# VAR-PBB_v01.net
KiCad netlist of a schematic drawn in EAGLE
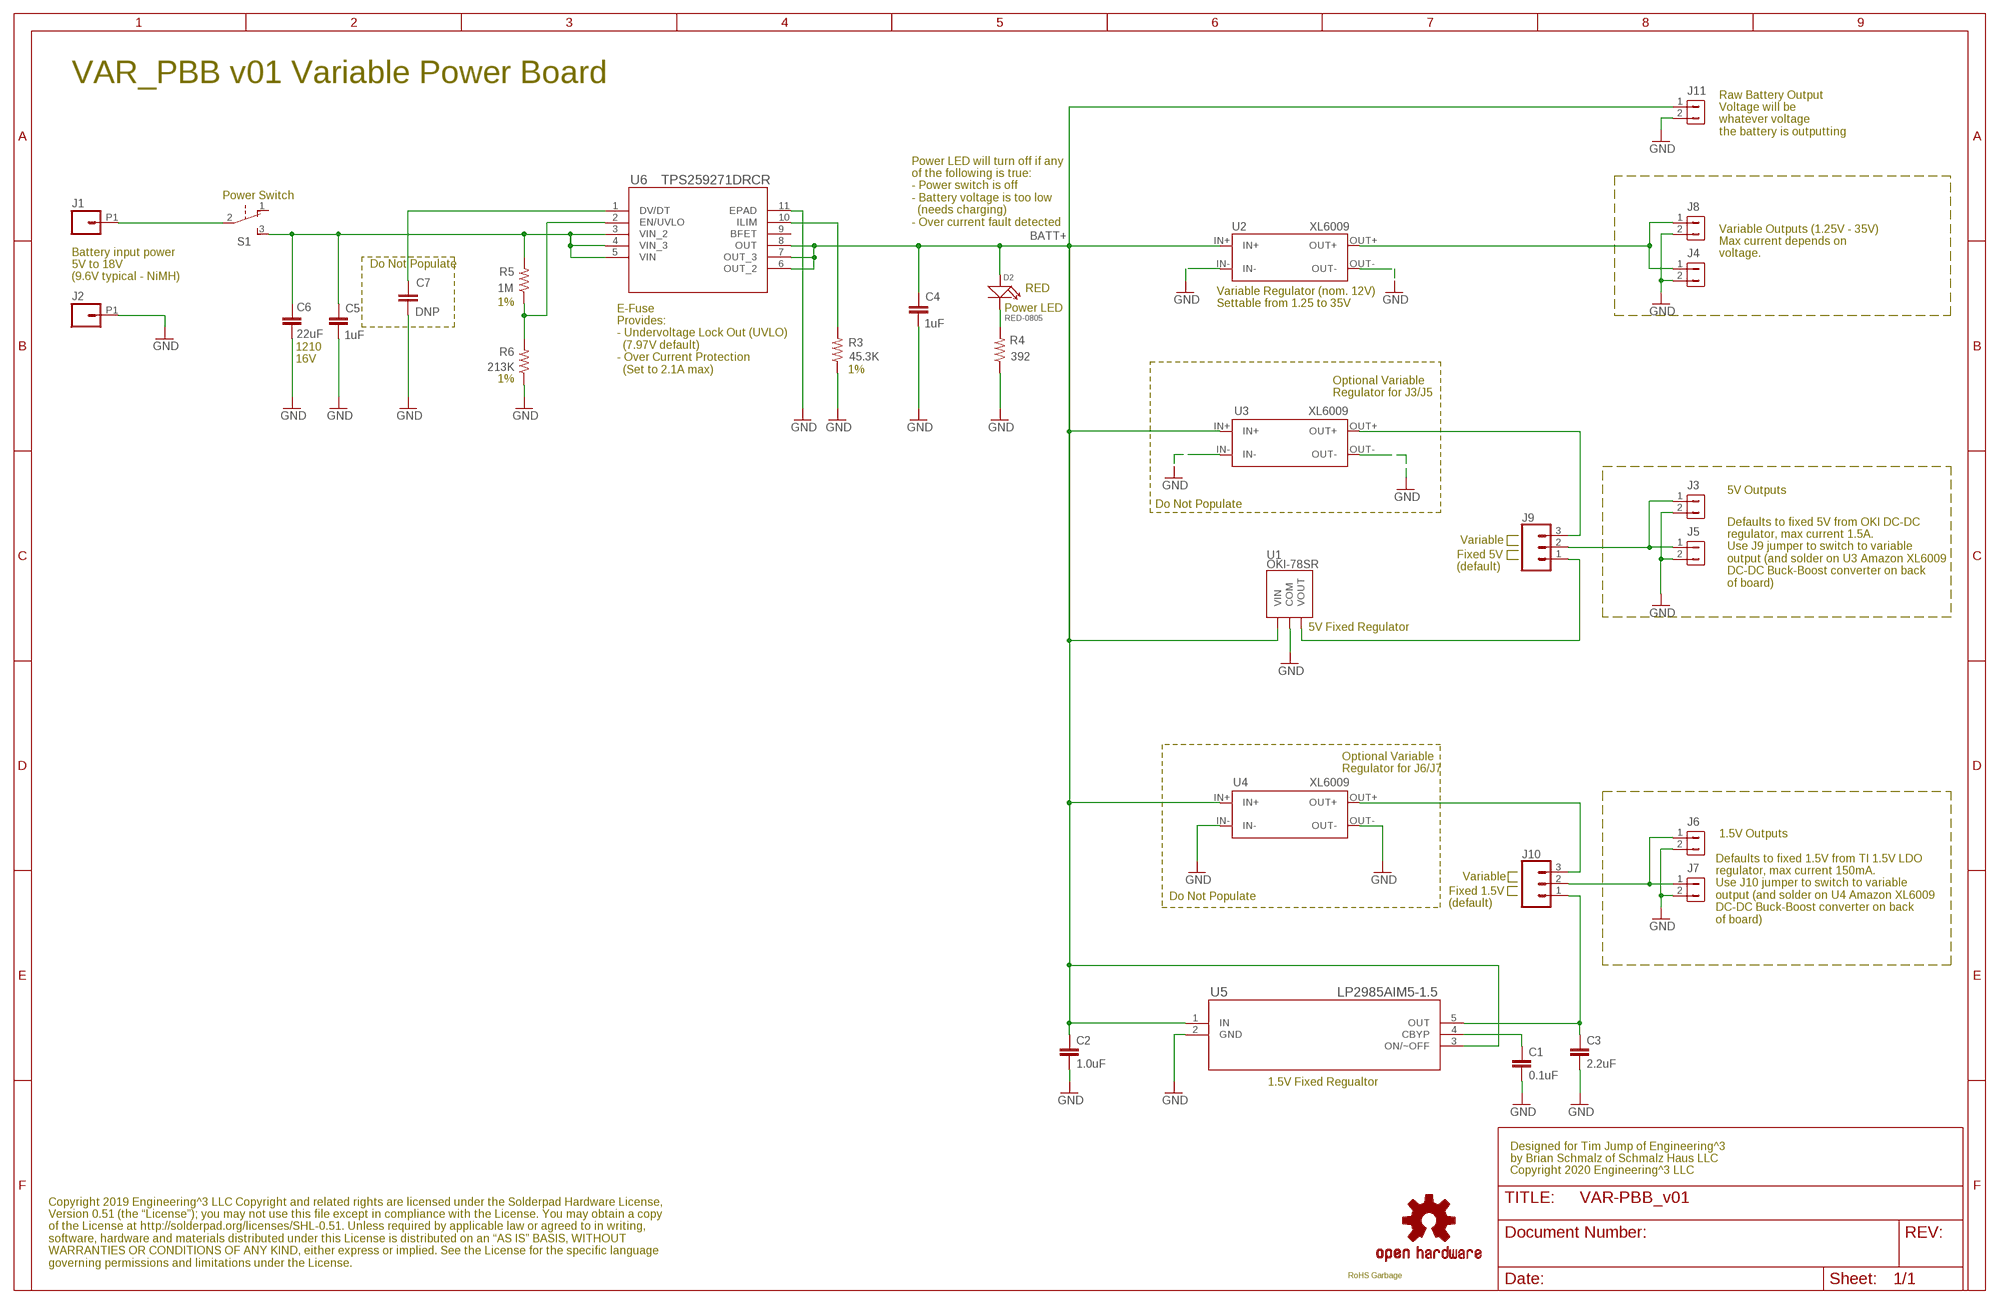
[diagram p0: schematic, sheet 1]

(export (version "E")
  (design (tool "Eeschema 10.0.6"))
  (components
    (comp (ref "C1")
      (value "0.1uF")
      (footprint "eagle-import:0603")
      (libsource (lib "eagle-import") (part "0.1UF-0603-25V-5%"))
    )
    (comp (ref "C2")
      (value "1.0uF")
      (footprint "eagle-import:0603")
      (libsource (lib "eagle-import") (part "1.0UF-0603-16V-10%"))
    )
    (comp (ref "C3")
      (value "2.2uF")
      (footprint "eagle-import:0603")
      (libsource (lib "eagle-import") (part "2.2UF-0603-10V-20%"))
    )
    (comp (ref "C4")
      (value "1uF")
      (footprint "eagle-import:0603")
      (libsource (lib "eagle-import") (part "0.1UF-0603-25V-5%"))
    )
    (comp (ref "C5")
      (value "1uF")
      (footprint "eagle-import:0603")
      (libsource (lib "eagle-import") (part "0.1UF-0603-25V-5%"))
    )
    (comp (ref "C6")
      (value "22uF")
      (footprint "eagle-import:1210")
      (libsource (lib "eagle-import") (part "22UF-1210-16V-20%"))
    )
    (comp (ref "C7")
      (value "DNP")
      (footprint "eagle-import:0603")
      (libsource (lib "eagle-import") (part "0.1UF-0603-25V-5%"))
    )
    (comp (ref "D2")
      (value "RED-0805")
      (footprint "eagle-import:LED-0805")
      (fields (field (name "MPN") "17-215SURC/S530-A2/TR8"))
      (libsource (lib "eagle-import") (part "SMD-LED-CLEAR-RED(0805)"))
    )
    (comp (ref "J1")
      (value "ANDERSON_POWER_POLE")
      (footprint "eagle-import:ANDERSON_POWER_POLE")
      (libsource (lib "eagle-import") (part "ANDERSON_POWER_POLE"))
    )
    (comp (ref "J2")
      (value "ANDERSON_POWER_POLE")
      (footprint "eagle-import:ANDERSON_POWER_POLE")
      (libsource (lib "eagle-import") (part "ANDERSON_POWER_POLE"))
    )
    (comp (ref "J3")
      (value "CON1X2_SHROUDED")
      (footprint "eagle-import:HEADER_1X2_SHROUDED")
      (libsource (lib "eagle-import") (part "CON1X2_SHROUDED"))
    )
    (comp (ref "J4")
      (value "CON1X2_SHROUDED")
      (footprint "eagle-import:HEADER_1X2_SHROUDED")
      (libsource (lib "eagle-import") (part "CON1X2_SHROUDED"))
    )
    (comp (ref "J5")
      (value "CON1X2_SHROUDED")
      (footprint "eagle-import:HEADER_1X2_SHROUDED")
      (libsource (lib "eagle-import") (part "CON1X2_SHROUDED"))
    )
    (comp (ref "J6")
      (value "CON1X2_SHROUDED")
      (footprint "eagle-import:HEADER_1X2_SHROUDED")
      (libsource (lib "eagle-import") (part "CON1X2_SHROUDED"))
    )
    (comp (ref "J7")
      (value "CON1X2_SHROUDED")
      (footprint "eagle-import:HEADER_1X2_SHROUDED")
      (libsource (lib "eagle-import") (part "CON1X2_SHROUDED"))
    )
    (comp (ref "J8")
      (value "CON1X2_SHROUDED")
      (footprint "eagle-import:HEADER_1X2_SHROUDED")
      (libsource (lib "eagle-import") (part "CON1X2_SHROUDED"))
    )
    (comp (ref "J9")
      (value "CONN_03")
      (footprint "eagle-import:1X03")
      (libsource (lib "eagle-import") (part "CONN_03"))
    )
    (comp (ref "J10")
      (value "CONN_03")
      (footprint "eagle-import:1X03")
      (libsource (lib "eagle-import") (part "CONN_03"))
    )
    (comp (ref "J11")
      (value "CON1X2_SHROUDED")
      (footprint "eagle-import:HEADER_1X2_SHROUDED")
      (libsource (lib "eagle-import") (part "CON1X2_SHROUDED"))
    )
    (comp (ref "LOGO2")
      (value "OSHW-LOGOM")
      (footprint "eagle-import:OSHW-LOGO-M")
      (libsource (lib "eagle-import") (part "OSHW-LOGOM"))
    )
    (comp (ref "R3")
      (value "45.3K")
      (footprint "eagle-import:0603")
      (libsource (lib "eagle-import") (part "RESISTOR0603"))
    )
    (comp (ref "R4")
      (value "392")
      (footprint "eagle-import:0603")
      (libsource (lib "eagle-import") (part "RESISTOR0603"))
    )
    (comp (ref "R5")
      (value "1M")
      (footprint "eagle-import:0603")
      (libsource (lib "eagle-import") (part "RESISTOR0603"))
    )
    (comp (ref "R6")
      (value "213K")
      (footprint "eagle-import:0603")
      (libsource (lib "eagle-import") (part "RESISTOR0603"))
    )
    (comp (ref "S1")
      (value "SWITCH_SLIDE_ON_ON")
      (footprint "eagle-import:SWITCH_SLIDE_RA")
      (libsource (lib "eagle-import") (part "SWITCH_SLIDE_ON_ON"))
    )
    (comp (ref "U$6")
      (value "ROHS_GARBAGE")
      (footprint "eagle-import:ROHS_GARBAGE_5MM")
      (libsource (lib "eagle-import") (part "ROHS_GARBAGE"))
    )
    (comp (ref "U1")
      (value "OKI-78SR")
      (footprint "eagle-import:OKI-78SR_REGULATOR_HORIZONTAL")
      (libsource (lib "eagle-import") (part "OKI-78SR"))
    )
    (comp (ref "U2")
      (value "XL6009")
      (footprint "eagle-import:XL6009_MODULE")
      (libsource (lib "eagle-import") (part "XL6009"))
    )
    (comp (ref "U3")
      (value "XL6009")
      (footprint "eagle-import:XL6009_MODULE")
      (libsource (lib "eagle-import") (part "XL6009"))
    )
    (comp (ref "U4")
      (value "XL6009")
      (footprint "eagle-import:XL6009_MODULE")
      (libsource (lib "eagle-import") (part "XL6009"))
    )
    (comp (ref "U5")
      (value "LP2985AIM5-1.5")
      (footprint "eagle-import:MF05A")
      (fields (field (name "COPYRIGHT") "Copyright (C) 2018 Accelerated Designs. All rights reserved"))
      (libsource (lib "eagle-import") (part "LP2985AIM5-1.5"))
    )
    (comp (ref "U6")
      (value "TPS259271DRCR")
      (footprint "eagle-import:DRC10_1P65X2P40")
      (fields (field (name "COPYRIGHT") "Copyright (C) 2018 Accelerated Designs. All rights reserved"))
      (libsource (lib "eagle-import") (part "TPS259271DRCR"))
    )
  )
  (nets
    (net (code "1") (name "/BATT+") (class "Default")
      (node (ref "C2") (pin "1") (pinfunction "1_1") (pintype "passive"))
      (node (ref "C4") (pin "2") (pinfunction "2_2") (pintype "passive"))
      (node (ref "D2") (pin "+") (pinfunction "+_+") (pintype "passive"))
      (node (ref "J11") (pin "1") (pinfunction "1_1") (pintype "passive"))
      (node (ref "U1") (pin "P$1") (pinfunction "VIN_P$1") (pintype "bidirectional"))
      (node (ref "U2") (pin "IN+") (pinfunction "IN+_IN+") (pintype "bidirectional"))
      (node (ref "U3") (pin "IN+") (pinfunction "IN+_IN+") (pintype "bidirectional"))
      (node (ref "U4") (pin "IN+") (pinfunction "IN+_IN+") (pintype "bidirectional"))
      (node (ref "U5") (pin "1") (pinfunction "IN_1") (pintype "power_in"))
      (node (ref "U5") (pin "3") (pinfunction "ON/~{OFF}_3") (pintype "input"))
      (node (ref "U6") (pin "6") (pinfunction "OUT_2_6") (pintype "output"))
      (node (ref "U6") (pin "7") (pinfunction "OUT_3_7") (pintype "output"))
      (node (ref "U6") (pin "8") (pinfunction "OUT_8") (pintype "output"))
    )
    (net (code "2") (name "GND") (class "Default")
      (node (ref "C1") (pin "2") (pinfunction "2_2") (pintype "passive"))
      (node (ref "C2") (pin "2") (pinfunction "2_2") (pintype "passive"))
      (node (ref "C3") (pin "2") (pinfunction "2_2") (pintype "passive"))
      (node (ref "C4") (pin "1") (pinfunction "1_1") (pintype "passive"))
      (node (ref "C5") (pin "1") (pinfunction "1_1") (pintype "passive"))
      (node (ref "C6") (pin "2") (pinfunction "2_2") (pintype "passive"))
      (node (ref "C7") (pin "1") (pinfunction "1_1") (pintype "passive"))
      (node (ref "J11") (pin "2") (pinfunction "2_2") (pintype "passive"))
      (node (ref "J2") (pin "P1") (pinfunction "5_P1") (pintype "passive"))
      (node (ref "J3") (pin "2") (pinfunction "2_2") (pintype "passive"))
      (node (ref "J4") (pin "2") (pinfunction "2_2") (pintype "passive"))
      (node (ref "J5") (pin "2") (pinfunction "2_2") (pintype "passive"))
      (node (ref "J6") (pin "2") (pinfunction "2_2") (pintype "passive"))
      (node (ref "J7") (pin "2") (pinfunction "2_2") (pintype "passive"))
      (node (ref "J8") (pin "2") (pinfunction "2_2") (pintype "passive"))
      (node (ref "R3") (pin "1") (pinfunction "1_1") (pintype "passive"))
      (node (ref "R4") (pin "1") (pinfunction "1_1") (pintype "passive"))
      (node (ref "R6") (pin "1") (pinfunction "1_1") (pintype "passive"))
      (node (ref "U1") (pin "P$2") (pinfunction "COM_P$2") (pintype "bidirectional"))
      (node (ref "U2") (pin "IN-") (pinfunction "IN-_IN-") (pintype "bidirectional"))
      (node (ref "U2") (pin "OUT-") (pinfunction "OUT-_OUT-") (pintype "bidirectional"))
      (node (ref "U3") (pin "IN-") (pinfunction "IN-_IN-") (pintype "bidirectional"))
      (node (ref "U3") (pin "OUT-") (pinfunction "OUT-_OUT-") (pintype "bidirectional"))
      (node (ref "U4") (pin "IN-") (pinfunction "IN-_IN-") (pintype "bidirectional"))
      (node (ref "U4") (pin "OUT-") (pinfunction "OUT-_OUT-") (pintype "bidirectional"))
      (node (ref "U5") (pin "2") (pinfunction "GND_2") (pintype "power_in"))
      (node (ref "U6") (pin "11") (pinfunction "EPAD_11") (pintype "passive"))
    )
    (net (code "3") (name "Net-(D2-Pad-)") (class "Default")
      (node (ref "D2") (pin "-") (pinfunction "-_-") (pintype "passive"))
      (node (ref "R4") (pin "2") (pinfunction "2_2") (pintype "passive"))
    )
    (net (code "4") (name "Net-(J1-5)") (class "Default")
      (node (ref "J1") (pin "P1") (pinfunction "5_P1") (pintype "passive"))
      (node (ref "S1") (pin "2") (pinfunction "P_2") (pintype "passive"))
    )
    (net (code "5") (name "Net-(J3-Pad1)") (class "Default")
      (node (ref "J3") (pin "1") (pinfunction "1_1") (pintype "passive"))
      (node (ref "J5") (pin "1") (pinfunction "1_1") (pintype "passive"))
      (node (ref "J9") (pin "2") (pinfunction "2_2") (pintype "passive"))
    )
    (net (code "6") (name "Net-(J4-Pad1)") (class "Default")
      (node (ref "J4") (pin "1") (pinfunction "1_1") (pintype "passive"))
      (node (ref "J8") (pin "1") (pinfunction "1_1") (pintype "passive"))
      (node (ref "U2") (pin "OUT+") (pinfunction "OUT+_OUT+") (pintype "bidirectional"))
    )
    (net (code "7") (name "Net-(J9-Pad3)") (class "Default")
      (node (ref "J9") (pin "3") (pinfunction "3_3") (pintype "passive"))
      (node (ref "U3") (pin "OUT+") (pinfunction "OUT+_OUT+") (pintype "bidirectional"))
    )
    (net (code "8") (name "Net-(J10-Pad2)") (class "Default")
      (node (ref "J10") (pin "2") (pinfunction "2_2") (pintype "passive"))
      (node (ref "J6") (pin "1") (pinfunction "1_1") (pintype "passive"))
      (node (ref "J7") (pin "1") (pinfunction "1_1") (pintype "passive"))
    )
    (net (code "9") (name "Net-(J10-Pad3)") (class "Default")
      (node (ref "J10") (pin "3") (pinfunction "3_3") (pintype "passive"))
      (node (ref "U4") (pin "OUT+") (pinfunction "OUT+_OUT+") (pintype "bidirectional"))
    )
    (net (code "10") (name "Net-(S1-S)") (class "Default")
      (node (ref "C5") (pin "2") (pinfunction "2_2") (pintype "passive"))
      (node (ref "C6") (pin "1") (pinfunction "1_1") (pintype "passive"))
      (node (ref "R5") (pin "2") (pinfunction "2_2") (pintype "passive"))
      (node (ref "S1") (pin "3") (pinfunction "S_3") (pintype "passive"))
      (node (ref "U6") (pin "3") (pinfunction "VIN_2_3") (pintype "passive"))
      (node (ref "U6") (pin "4") (pinfunction "VIN_3_4") (pintype "passive"))
      (node (ref "U6") (pin "5") (pinfunction "VIN_5") (pintype "passive"))
    )
    (net (code "11") (name "Net-(U1-VOUT)") (class "Default")
      (node (ref "J9") (pin "1") (pinfunction "1_1") (pintype "passive"))
      (node (ref "U1") (pin "P$3") (pinfunction "VOUT_P$3") (pintype "bidirectional"))
    )
    (net (code "12") (name "Net-(U5-CBYP)") (class "Default")
      (node (ref "C1") (pin "1") (pinfunction "1_1") (pintype "passive"))
      (node (ref "U5") (pin "4") (pinfunction "CBYP_4") (pintype "passive"))
    )
    (net (code "13") (name "Net-(U5-OUT)") (class "Default")
      (node (ref "C3") (pin "1") (pinfunction "1_1") (pintype "passive"))
      (node (ref "J10") (pin "1") (pinfunction "1_1") (pintype "passive"))
      (node (ref "U5") (pin "5") (pinfunction "OUT_5") (pintype "power_in"))
    )
    (net (code "14") (name "Net-(U6-DV{slash}DT)") (class "Default")
      (node (ref "C7") (pin "2") (pinfunction "2_2") (pintype "passive"))
      (node (ref "U6") (pin "1") (pinfunction "DV/DT_1") (pintype "passive"))
    )
    (net (code "15") (name "Net-(U6-EN{slash}UVLO)") (class "Default")
      (node (ref "R5") (pin "1") (pinfunction "1_1") (pintype "passive"))
      (node (ref "R6") (pin "2") (pinfunction "2_2") (pintype "passive"))
      (node (ref "U6") (pin "2") (pinfunction "EN/UVLO_2") (pintype "passive"))
    )
    (net (code "16") (name "Net-(U6-ILIM)") (class "Default")
      (node (ref "R3") (pin "2") (pinfunction "2_2") (pintype "passive"))
      (node (ref "U6") (pin "10") (pinfunction "ILIM_10") (pintype "passive"))
    )
    (net (code "17") (name "unconnected-(S1-O-Pad1)") (class "Default")
      (node (ref "S1") (pin "1") (pinfunction "O_1") (pintype "passive"))
    )
    (net (code "18") (name "unconnected-(U6-BFET-Pad9)") (class "Default")
      (node (ref "U6") (pin "9") (pinfunction "BFET_9") (pintype "passive"))
    )
  )
)
